# Possible_board_Schematic.net
KiCad netlist of a schematic drawn in EAGLE
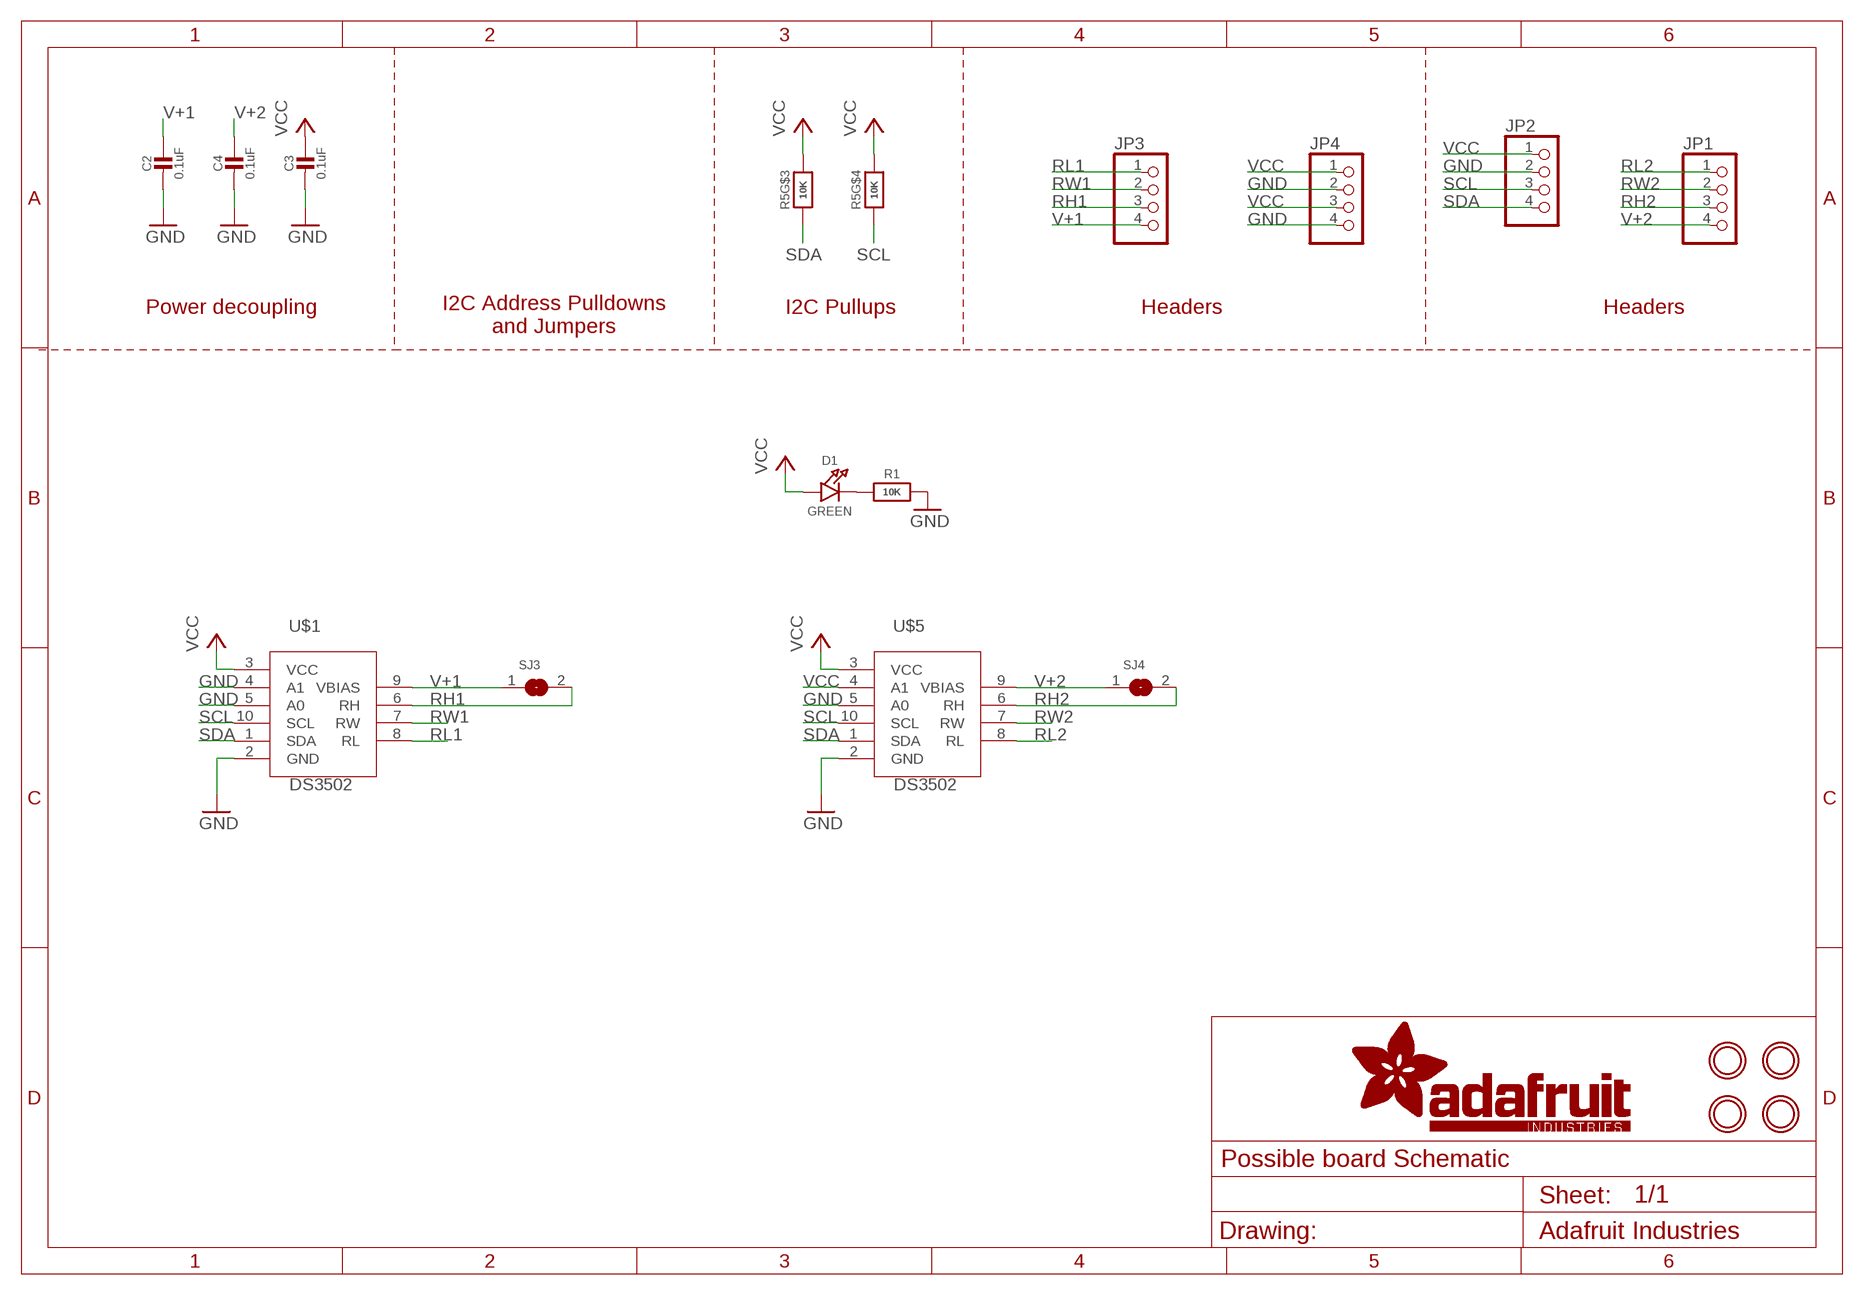
[diagram p0: schematic, sheet 1]

(export (version "E")
  (design (tool "Eeschema 10.0.6"))
  (components
    (comp (ref "C2")
      (value "0.1uF")
      (footprint "eagle-import:0603-NO")
      (libsource (lib "eagle-import") (part "CAP_CERAMIC0603_NO"))
    )
    (comp (ref "C3")
      (value "0.1uF")
      (footprint "eagle-import:0603-NO")
      (libsource (lib "eagle-import") (part "CAP_CERAMIC0603_NO"))
    )
    (comp (ref "C4")
      (value "0.1uF")
      (footprint "eagle-import:0603-NO")
      (libsource (lib "eagle-import") (part "CAP_CERAMIC0603_NO"))
    )
    (comp (ref "D1")
      (value "GREEN")
      (footprint "eagle-import:CHIPLED_0603_NOOUTLINE")
      (libsource (lib "eagle-import") (part "LED0603_NOOUTLINE"))
    )
    (comp (ref "JP1")
      (value "HEADER-1X4ROUND")
      (footprint "eagle-import:1X04_ROUND")
      (libsource (lib "eagle-import") (part "HEADER-1X4ROUND"))
    )
    (comp (ref "JP2")
      (value "HEADER-1X4ROUND")
      (footprint "eagle-import:1X04_ROUND")
      (libsource (lib "eagle-import") (part "HEADER-1X4ROUND"))
    )
    (comp (ref "JP3")
      (value "HEADER-1X4ROUND")
      (footprint "eagle-import:1X04_ROUND")
      (libsource (lib "eagle-import") (part "HEADER-1X4ROUND"))
    )
    (comp (ref "JP4")
      (value "HEADER-1X4ROUND")
      (footprint "eagle-import:1X04_ROUND")
      (libsource (lib "eagle-import") (part "HEADER-1X4ROUND"))
    )
    (comp (ref "R1")
      (value "10K")
      (footprint "eagle-import:0603-NO")
      (libsource (lib "eagle-import") (part "RESISTOR_0603_NOOUT"))
    )
    (comp (ref "R5")
      (value "10K")
      (footprint "eagle-import:RESPACK_4X0603")
      (libsource (lib "eagle-import") (part "RESISTOR_4PACK"))
    )
    (comp (ref "SJ3")
      (value "SOLDERJUMPERCLOSED")
      (footprint "eagle-import:SOLDERJUMPER_CLOSEDWIRE")
      (libsource (lib "eagle-import") (part "SOLDERJUMPERCLOSED"))
    )
    (comp (ref "SJ4")
      (value "SOLDERJUMPERCLOSED")
      (footprint "eagle-import:SOLDERJUMPER_CLOSEDWIRE")
      (libsource (lib "eagle-import") (part "SOLDERJUMPERCLOSED"))
    )
    (comp (ref "U$1")
      (value "DS3502")
      (footprint "eagle-import:MSOP10")
      (libsource (lib "eagle-import") (part "DS3502"))
    )
    (comp (ref "U$2")
      (value "MOUNTINGHOLE2.5")
      (footprint "eagle-import:MOUNTINGHOLE_2.5_PLATED")
      (libsource (lib "eagle-import") (part "MOUNTINGHOLE2.5"))
    )
    (comp (ref "U$3")
      (value "MOUNTINGHOLE2.5")
      (footprint "eagle-import:MOUNTINGHOLE_2.5_PLATED")
      (libsource (lib "eagle-import") (part "MOUNTINGHOLE2.5"))
    )
    (comp (ref "U$5")
      (value "DS3502")
      (footprint "eagle-import:MSOP10")
      (libsource (lib "eagle-import") (part "DS3502"))
    )
    (comp (ref "U$6")
      (value "MOUNTINGHOLE2.5")
      (footprint "eagle-import:MOUNTINGHOLE_2.5_PLATED")
      (libsource (lib "eagle-import") (part "MOUNTINGHOLE2.5"))
    )
    (comp (ref "U$7")
      (value "MOUNTINGHOLE2.5")
      (footprint "eagle-import:MOUNTINGHOLE_2.5_PLATED")
      (libsource (lib "eagle-import") (part "MOUNTINGHOLE2.5"))
    )
  )
  (nets
    (net (code "1") (name "/RH1") (class "Default")
      (node (ref "JP3") (pin "3") (pinfunction "3_3") (pintype "passive"))
      (node (ref "SJ3") (pin "2") (pinfunction "2_2") (pintype "passive"))
      (node (ref "U$1") (pin "6") (pinfunction "RH_6") (pintype "passive"))
    )
    (net (code "2") (name "/RH2") (class "Default")
      (node (ref "JP1") (pin "3") (pinfunction "3_3") (pintype "passive"))
      (node (ref "SJ4") (pin "2") (pinfunction "2_2") (pintype "passive"))
      (node (ref "U$5") (pin "6") (pinfunction "RH_6") (pintype "passive"))
    )
    (net (code "3") (name "/RL1") (class "Default")
      (node (ref "JP3") (pin "1") (pinfunction "1_1") (pintype "passive"))
      (node (ref "U$1") (pin "8") (pinfunction "RL_8") (pintype "passive"))
    )
    (net (code "4") (name "/RL2") (class "Default")
      (node (ref "JP1") (pin "1") (pinfunction "1_1") (pintype "passive"))
      (node (ref "U$5") (pin "8") (pinfunction "RL_8") (pintype "passive"))
    )
    (net (code "5") (name "/RW1") (class "Default")
      (node (ref "JP3") (pin "2") (pinfunction "2_2") (pintype "passive"))
      (node (ref "U$1") (pin "7") (pinfunction "RW_7") (pintype "passive"))
    )
    (net (code "6") (name "/RW2") (class "Default")
      (node (ref "JP1") (pin "2") (pinfunction "2_2") (pintype "passive"))
      (node (ref "U$5") (pin "7") (pinfunction "RW_7") (pintype "passive"))
    )
    (net (code "7") (name "/SCL") (class "Default")
      (node (ref "JP2") (pin "3") (pinfunction "3_3") (pintype "passive"))
      (node (ref "R5") (pin "4") (pinfunction "1_4") (pintype "passive"))
      (node (ref "U$1") (pin "10") (pinfunction "SCL_10") (pintype "input"))
      (node (ref "U$5") (pin "10") (pinfunction "SCL_10") (pintype "input"))
    )
    (net (code "8") (name "/SDA") (class "Default")
      (node (ref "JP2") (pin "4") (pinfunction "4_4") (pintype "passive"))
      (node (ref "R5") (pin "3") (pinfunction "1_3") (pintype "passive"))
      (node (ref "U$1") (pin "1") (pinfunction "SDA_1") (pintype "bidirectional"))
      (node (ref "U$5") (pin "1") (pinfunction "SDA_1") (pintype "bidirectional"))
    )
    (net (code "9") (name "/V+1") (class "Default")
      (node (ref "C2") (pin "1") (pinfunction "1_1") (pintype "passive"))
      (node (ref "JP3") (pin "4") (pinfunction "4_4") (pintype "passive"))
      (node (ref "SJ3") (pin "1") (pinfunction "1_1") (pintype "passive"))
      (node (ref "U$1") (pin "9") (pinfunction "VBIAS_9") (pintype "power_in"))
    )
    (net (code "10") (name "/V+2") (class "Default")
      (node (ref "C4") (pin "1") (pinfunction "1_1") (pintype "passive"))
      (node (ref "JP1") (pin "4") (pinfunction "4_4") (pintype "passive"))
      (node (ref "SJ4") (pin "1") (pinfunction "1_1") (pintype "passive"))
      (node (ref "U$5") (pin "9") (pinfunction "VBIAS_9") (pintype "power_in"))
    )
    (net (code "11") (name "GND") (class "Default")
      (node (ref "C2") (pin "2") (pinfunction "2_2") (pintype "passive"))
      (node (ref "C3") (pin "2") (pinfunction "2_2") (pintype "passive"))
      (node (ref "C4") (pin "2") (pinfunction "2_2") (pintype "passive"))
      (node (ref "JP2") (pin "2") (pinfunction "2_2") (pintype "passive"))
      (node (ref "JP4") (pin "2") (pinfunction "2_2") (pintype "passive"))
      (node (ref "JP4") (pin "4") (pinfunction "4_4") (pintype "passive"))
      (node (ref "R1") (pin "2") (pinfunction "2_2") (pintype "passive"))
      (node (ref "U$1") (pin "2") (pinfunction "GND_2") (pintype "power_in"))
      (node (ref "U$1") (pin "4") (pinfunction "A1_4") (pintype "input"))
      (node (ref "U$1") (pin "5") (pinfunction "A0_5") (pintype "input"))
      (node (ref "U$5") (pin "2") (pinfunction "GND_2") (pintype "power_in"))
      (node (ref "U$5") (pin "5") (pinfunction "A0_5") (pintype "input"))
    )
    (net (code "12") (name "Net-(D1-PadC)") (class "Default")
      (node (ref "D1") (pin "C") (pinfunction "C_C") (pintype "passive"))
      (node (ref "R1") (pin "1") (pinfunction "1_1") (pintype "passive"))
    )
    (net (code "13") (name "VCC") (class "Default")
      (node (ref "C3") (pin "1") (pinfunction "1_1") (pintype "passive"))
      (node (ref "D1") (pin "A") (pinfunction "A_A") (pintype "passive"))
      (node (ref "JP2") (pin "1") (pinfunction "1_1") (pintype "passive"))
      (node (ref "JP4") (pin "1") (pinfunction "1_1") (pintype "passive"))
      (node (ref "JP4") (pin "3") (pinfunction "3_3") (pintype "passive"))
      (node (ref "R5") (pin "5") (pinfunction "2_5") (pintype "passive"))
      (node (ref "R5") (pin "6") (pinfunction "2_6") (pintype "passive"))
      (node (ref "U$1") (pin "3") (pinfunction "VCC_3") (pintype "power_in"))
      (node (ref "U$5") (pin "3") (pinfunction "VCC_3") (pintype "power_in"))
      (node (ref "U$5") (pin "4") (pinfunction "A1_4") (pintype "input"))
    )
  )
)
